# AL1_Signal_Isolation.net
KiCad netlist of a schematic drawn in Altium Designer
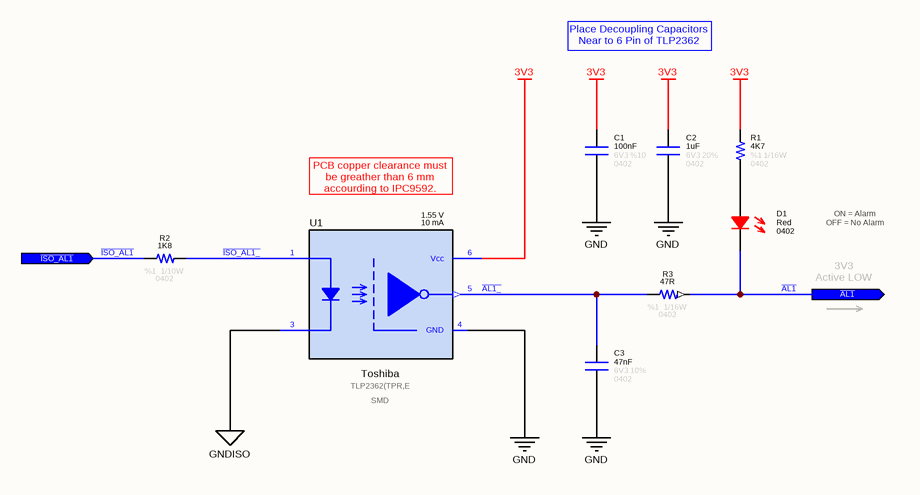
[diagram p0: AL1 Signal Isolation.SchDoc]

(export (version "E")
  (design (tool "Eeschema 10.0.6"))
  (components
    (comp (ref "C1")
      (value "100nF")
      (footprint "CAPACITOR_0402")
      (description "Capacitor - 100nF [0402-6V3] (Ceramic)")
      (fields
        (field (name "MANUFACTURER PART NUMBER") "04026D104KAT4A")
        (field (name "TOLERANCE") "%10")
        (field (name "VOLTAGE") "6V3")
        (field (name "CASE") "0402")
        (field (name "Comment") "Capacitor - 100nF [0402] (Ceramic)")
      )
      (libsource (lib "Akkoyun") (part "Capacitor - 100nF [0402-6V3]"))
    )
    (comp (ref "C2")
      (value "1uF")
      (footprint "CAPACITOR_0402")
      (description "Capacitor (MLCC) - 1uF / 6V3 / 0402")
      (fields
        (field (name "MANUFACTURER PART NUMBER") "GRM153R60J105ME95D")
        (field (name "TOLERANCE") "20%")
        (field (name "CASE") "0402")
        (field (name "VOLTAGE") "6V3")
        (field (name "Comment") "Capacitor - 1uF [0402] (MLCC)")
      )
      (libsource (lib "Akkoyun") (part "Capacitor - 1uF [0402-6V3]"))
    )
    (comp (ref "C3")
      (value "47nF")
      (footprint "CAPACITOR_0402")
      (description "Capacitor (MLCC) - 47nF / 6V3 / 0402")
      (fields
        (field (name "MANUFACTURER PART NUMBER") "04026D473KAT2A")
        (field (name "TOLERANCE") "10%")
        (field (name "CASE") "0402")
        (field (name "VOLTAGE") "6V3")
        (field (name "Comment") "Capacitor - 47nF [0402] (MLCC)")
      )
      (libsource (lib "Akkoyun") (part "Capacitor - 47nF [0402-6V3]"))
    )
    (comp (ref "D1")
      (value "SMD LED (Red)")
      (footprint "LED_0402")
      (description "Standard LEDs - SMD MINI-MOLD ULTRA COMPACT RED")
      (fields
        (field (name "MANUFACTURER PART NUMBER") "SML-P12VTT86R")
        (field (name "CASE") "0402")
        (field (name "COLOR") "Red")
      )
      (libsource (lib "Akkoyun") (part "Diode - LED (0402-Red)"))
    )
    (comp (ref "R1")
      (value "4K7")
      (footprint "RESISTOR_0402")
      (description "Thick Film Resistors - SMD 1/16 W 4.7 KOhm 1%")
      (fields
        (field (name "MANUFACTURER PART NUMBER") "CRCW04024K70FKED")
        (field (name "TOLERANCE") "%1")
        (field (name "CASE") "0402")
        (field (name "POWER") "1/16W")
        (field (name "Comment") "4K7 - 0402 - %1 - 1/16W")
      )
      (libsource (lib "Akkoyun") (part "Resistor - 4K7 [0402]"))
    )
    (comp (ref "R2")
      (value "1K8")
      (footprint "RESISTOR_0402")
      (description "Thick Film Resistors - SMD 1/16 W 1.8 KOhm 1%")
      (fields
        (field (name "MANUFACTURER PART NUMBER") "CRCW04021K80FKED")
        (field (name "TOLERANCE") "%1")
        (field (name "CASE") "0402")
        (field (name "POWER") "1/10W")
        (field (name "Comment") "1K8 - 0402 - %1 - 1/16W")
      )
      (libsource (lib "Akkoyun") (part "Resistor - 1K8 [0402]"))
    )
    (comp (ref "R3")
      (value "47R")
      (footprint "RESISTOR_0402")
      (description "Thick Film Resistors - SMD 1/16 W 47 Ohm 1%")
      (fields
        (field (name "MANUFACTURER PART NUMBER") "CRCW040247R0FKED")
        (field (name "CASE") "0402")
        (field (name "TOLERANCE") "%1")
        (field (name "POWER") "1/16W")
        (field (name "Comment") "47R - 0402 - %1 - 1/16W")
      )
      (libsource (lib "Akkoyun") (part "Resistor - 47R [0402]"))
    )
    (comp (ref "U1")
      (value "TLP2362(TPR,E")
      (footprint "TLP2362")
      (description "High Speed Optocouplers 3750 Vrms 10MBd 4mA 2.7 to 5.5V LED")
      (fields
        (field (name "IF - FORWARD CURRENT") "10 mA")
        (field (name "VF - FORWARD VOLTAGE") "1.55 V")
        (field (name "MANUFACTURER NAME") "Toshiba")
        (field (name "MANUFACTURER PART NUMBER") "TLP2362(TPR,E")
        (field (name "CASE") "SMD")
      )
      (libsource (lib "Akkoyun") (part "IC - TLP2362"))
    )
  )
  (nets
    (net (code "1") (name "/~{AL1_}") (class "Default")
      (node (ref "C3") (pin "2") (pinfunction "2_2") (pintype "passive"))
      (node (ref "R3") (pin "2") (pinfunction "2_2") (pintype "passive"))
      (node (ref "U1") (pin "5") (pinfunction "Output_5") (pintype "output"))
    )
    (net (code "2") (name "/~{AL1}") (class "Default")
      (node (ref "D1") (pin "1") (pinfunction "1_1") (pintype "passive"))
      (node (ref "R3") (pin "1") (pinfunction "1_1") (pintype "output"))
    )
    (net (code "3") (name "/~{ISO_AL1_}") (class "Default")
      (node (ref "R2") (pin "1") (pinfunction "1_1") (pintype "passive"))
      (node (ref "U1") (pin "1") (pinfunction "Anode_1") (pintype "passive"))
    )
    (net (code "4") (name "/~{ISO_AL1}") (class "Default")
      (node (ref "R2") (pin "2") (pinfunction "2_2") (pintype "passive"))
    )
    (net (code "5") (name "3V3") (class "Default")
      (node (ref "C1") (pin "2") (pinfunction "2_2") (pintype "passive"))
      (node (ref "C2") (pin "2") (pinfunction "2_2") (pintype "passive"))
      (node (ref "R1") (pin "2") (pinfunction "2_2") (pintype "passive"))
      (node (ref "U1") (pin "6") (pinfunction "Vcc_6") (pintype "power_in"))
    )
    (net (code "6") (name "GND") (class "Default")
      (node (ref "C1") (pin "1") (pinfunction "1_1") (pintype "passive"))
      (node (ref "C2") (pin "1") (pinfunction "1_1") (pintype "passive"))
      (node (ref "C3") (pin "1") (pinfunction "1_1") (pintype "passive"))
      (node (ref "U1") (pin "4") (pinfunction "GND_4") (pintype "power_in"))
    )
    (net (code "7") (name "GNDISO") (class "Default")
      (node (ref "U1") (pin "3") (pinfunction "Cathode_3") (pintype "passive"))
    )
    (net (code "8") (name "Net-(D1-Pad2)") (class "Default")
      (node (ref "D1") (pin "2") (pinfunction "2_2") (pintype "passive"))
      (node (ref "R1") (pin "1") (pinfunction "1_1") (pintype "passive"))
    )
  )
)
